# qPCR_pcb_breakout_ADG731BSUZ.net
KiCad netlist of a schematic drawn in EAGLE
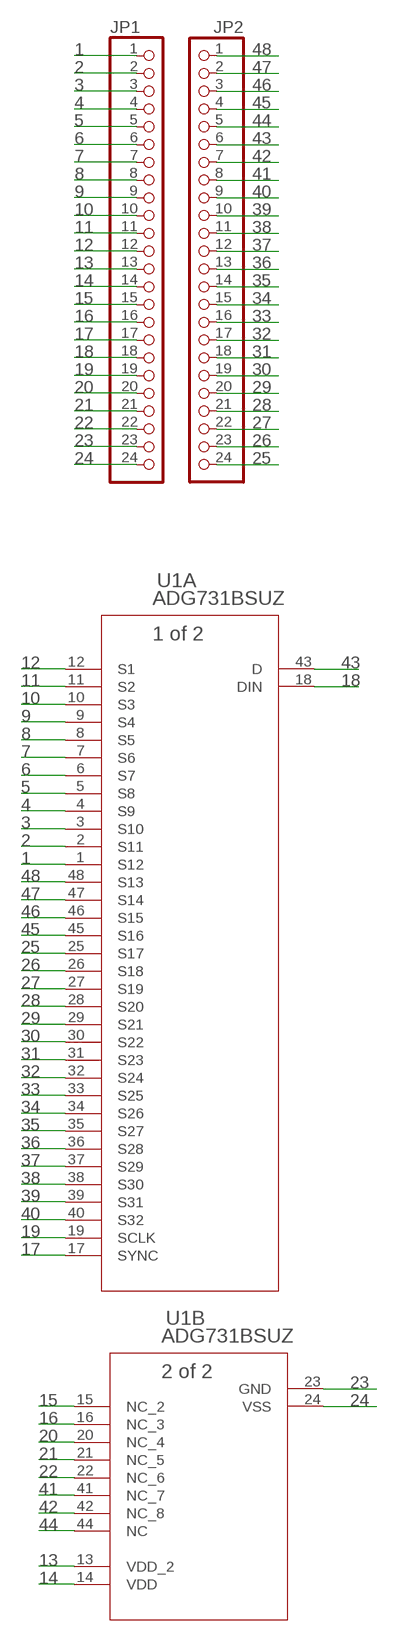
[diagram p0: schematic, sheet 1]

(export (version "E")
  (design (tool "Eeschema 10.0.6"))
  (components
    (comp (ref "JP1")
      (value "PINHD-1X24")
      (footprint "eagle-import:1X24")
      (libsource (lib "eagle-import") (part "PINHD-1X24"))
    )
    (comp (ref "JP2")
      (value "PINHD-1X24")
      (footprint "eagle-import:1X24")
      (libsource (lib "eagle-import") (part "PINHD-1X24"))
    )
    (comp (ref "U1")
      (value "ADG731BSUZ")
      (footprint "eagle-import:SU_48_ADI")
      (libsource (lib "eagle-import") (part "ADG731BSUZ"))
    )
  )
  (nets
    (net (code "1") (name "/1") (class "Default")
      (node (ref "JP1") (pin "1") (pinfunction "1_1") (pintype "passive"))
      (node (ref "U1") (pin "1") (pinfunction "S12_1") (pintype "passive"))
    )
    (net (code "2") (name "/2") (class "Default")
      (node (ref "JP1") (pin "2") (pinfunction "2_2") (pintype "passive"))
      (node (ref "U1") (pin "2") (pinfunction "S11_2") (pintype "passive"))
    )
    (net (code "3") (name "/3") (class "Default")
      (node (ref "JP1") (pin "3") (pinfunction "3_3") (pintype "passive"))
      (node (ref "U1") (pin "3") (pinfunction "S10_3") (pintype "passive"))
    )
    (net (code "4") (name "/4") (class "Default")
      (node (ref "JP1") (pin "4") (pinfunction "4_4") (pintype "passive"))
      (node (ref "U1") (pin "4") (pinfunction "S9_4") (pintype "passive"))
    )
    (net (code "5") (name "/5") (class "Default")
      (node (ref "JP1") (pin "5") (pinfunction "5_5") (pintype "passive"))
      (node (ref "U1") (pin "5") (pinfunction "S8_5") (pintype "passive"))
    )
    (net (code "6") (name "/6") (class "Default")
      (node (ref "JP1") (pin "6") (pinfunction "6_6") (pintype "passive"))
      (node (ref "U1") (pin "6") (pinfunction "S7_6") (pintype "passive"))
    )
    (net (code "7") (name "/7") (class "Default")
      (node (ref "JP1") (pin "7") (pinfunction "7_7") (pintype "passive"))
      (node (ref "U1") (pin "7") (pinfunction "S6_7") (pintype "passive"))
    )
    (net (code "8") (name "/8") (class "Default")
      (node (ref "JP1") (pin "8") (pinfunction "8_8") (pintype "passive"))
      (node (ref "U1") (pin "8") (pinfunction "S5_8") (pintype "passive"))
    )
    (net (code "9") (name "/9") (class "Default")
      (node (ref "JP1") (pin "9") (pinfunction "9_9") (pintype "passive"))
      (node (ref "U1") (pin "9") (pinfunction "S4_9") (pintype "passive"))
    )
    (net (code "10") (name "/10") (class "Default")
      (node (ref "JP1") (pin "10") (pinfunction "10_10") (pintype "passive"))
      (node (ref "U1") (pin "10") (pinfunction "S3_10") (pintype "passive"))
    )
    (net (code "11") (name "/11") (class "Default")
      (node (ref "JP1") (pin "11") (pinfunction "11_11") (pintype "passive"))
      (node (ref "U1") (pin "11") (pinfunction "S2_11") (pintype "passive"))
    )
    (net (code "12") (name "/12") (class "Default")
      (node (ref "JP1") (pin "12") (pinfunction "12_12") (pintype "passive"))
      (node (ref "U1") (pin "12") (pinfunction "S1_12") (pintype "passive"))
    )
    (net (code "13") (name "/13") (class "Default")
      (node (ref "JP1") (pin "13") (pinfunction "13_13") (pintype "passive"))
      (node (ref "U1") (pin "13") (pinfunction "VDD_2_13") (pintype "power_in"))
    )
    (net (code "14") (name "/14") (class "Default")
      (node (ref "JP1") (pin "14") (pinfunction "14_14") (pintype "passive"))
      (node (ref "U1") (pin "14") (pinfunction "VDD_14") (pintype "power_in"))
    )
    (net (code "15") (name "/15") (class "Default")
      (node (ref "JP1") (pin "15") (pinfunction "15_15") (pintype "passive"))
      (node (ref "U1") (pin "15") (pinfunction "NC_2_15") (pintype "passive"))
    )
    (net (code "16") (name "/16") (class "Default")
      (node (ref "JP1") (pin "16") (pinfunction "16_16") (pintype "passive"))
      (node (ref "U1") (pin "16") (pinfunction "NC_3_16") (pintype "passive"))
    )
    (net (code "17") (name "/17") (class "Default")
      (node (ref "JP1") (pin "17") (pinfunction "17_17") (pintype "passive"))
      (node (ref "U1") (pin "17") (pinfunction "SYNC_17") (pintype "passive"))
    )
    (net (code "18") (name "/18") (class "Default")
      (node (ref "JP1") (pin "18") (pinfunction "18_18") (pintype "passive"))
      (node (ref "U1") (pin "18") (pinfunction "DIN_18") (pintype "passive"))
    )
    (net (code "19") (name "/19") (class "Default")
      (node (ref "JP1") (pin "19") (pinfunction "19_19") (pintype "passive"))
      (node (ref "U1") (pin "19") (pinfunction "SCLK_19") (pintype "passive"))
    )
    (net (code "20") (name "/20") (class "Default")
      (node (ref "JP1") (pin "20") (pinfunction "20_20") (pintype "passive"))
      (node (ref "U1") (pin "20") (pinfunction "NC_4_20") (pintype "passive"))
    )
    (net (code "21") (name "/21") (class "Default")
      (node (ref "JP1") (pin "21") (pinfunction "21_21") (pintype "passive"))
      (node (ref "U1") (pin "21") (pinfunction "NC_5_21") (pintype "passive"))
    )
    (net (code "22") (name "/22") (class "Default")
      (node (ref "JP1") (pin "22") (pinfunction "22_22") (pintype "passive"))
      (node (ref "U1") (pin "22") (pinfunction "NC_6_22") (pintype "passive"))
    )
    (net (code "23") (name "/23") (class "Default")
      (node (ref "JP1") (pin "23") (pinfunction "23_23") (pintype "passive"))
      (node (ref "U1") (pin "23") (pinfunction "GND_23") (pintype "passive"))
    )
    (net (code "24") (name "/24") (class "Default")
      (node (ref "JP1") (pin "24") (pinfunction "24_24") (pintype "passive"))
      (node (ref "U1") (pin "24") (pinfunction "VSS_24") (pintype "power_in"))
    )
    (net (code "25") (name "/25") (class "Default")
      (node (ref "JP2") (pin "24") (pinfunction "24_24") (pintype "passive"))
      (node (ref "U1") (pin "25") (pinfunction "S17_25") (pintype "passive"))
    )
    (net (code "26") (name "/26") (class "Default")
      (node (ref "JP2") (pin "23") (pinfunction "23_23") (pintype "passive"))
      (node (ref "U1") (pin "26") (pinfunction "S18_26") (pintype "passive"))
    )
    (net (code "27") (name "/27") (class "Default")
      (node (ref "JP2") (pin "22") (pinfunction "22_22") (pintype "passive"))
      (node (ref "U1") (pin "27") (pinfunction "S19_27") (pintype "passive"))
    )
    (net (code "28") (name "/28") (class "Default")
      (node (ref "JP2") (pin "21") (pinfunction "21_21") (pintype "passive"))
      (node (ref "U1") (pin "28") (pinfunction "S20_28") (pintype "passive"))
    )
    (net (code "29") (name "/29") (class "Default")
      (node (ref "JP2") (pin "20") (pinfunction "20_20") (pintype "passive"))
      (node (ref "U1") (pin "29") (pinfunction "S21_29") (pintype "passive"))
    )
    (net (code "30") (name "/30") (class "Default")
      (node (ref "JP2") (pin "19") (pinfunction "19_19") (pintype "passive"))
      (node (ref "U1") (pin "30") (pinfunction "S22_30") (pintype "passive"))
    )
    (net (code "31") (name "/31") (class "Default")
      (node (ref "JP2") (pin "18") (pinfunction "18_18") (pintype "passive"))
      (node (ref "U1") (pin "31") (pinfunction "S23_31") (pintype "passive"))
    )
    (net (code "32") (name "/32") (class "Default")
      (node (ref "JP2") (pin "17") (pinfunction "17_17") (pintype "passive"))
      (node (ref "U1") (pin "32") (pinfunction "S24_32") (pintype "passive"))
    )
    (net (code "33") (name "/33") (class "Default")
      (node (ref "JP2") (pin "16") (pinfunction "16_16") (pintype "passive"))
      (node (ref "U1") (pin "33") (pinfunction "S25_33") (pintype "passive"))
    )
    (net (code "34") (name "/34") (class "Default")
      (node (ref "JP2") (pin "15") (pinfunction "15_15") (pintype "passive"))
      (node (ref "U1") (pin "34") (pinfunction "S26_34") (pintype "passive"))
    )
    (net (code "35") (name "/35") (class "Default")
      (node (ref "JP2") (pin "14") (pinfunction "14_14") (pintype "passive"))
      (node (ref "U1") (pin "35") (pinfunction "S27_35") (pintype "passive"))
    )
    (net (code "36") (name "/36") (class "Default")
      (node (ref "JP2") (pin "13") (pinfunction "13_13") (pintype "passive"))
      (node (ref "U1") (pin "36") (pinfunction "S28_36") (pintype "passive"))
    )
    (net (code "37") (name "/37") (class "Default")
      (node (ref "JP2") (pin "12") (pinfunction "12_12") (pintype "passive"))
      (node (ref "U1") (pin "37") (pinfunction "S29_37") (pintype "passive"))
    )
    (net (code "38") (name "/38") (class "Default")
      (node (ref "JP2") (pin "11") (pinfunction "11_11") (pintype "passive"))
      (node (ref "U1") (pin "38") (pinfunction "S30_38") (pintype "passive"))
    )
    (net (code "39") (name "/39") (class "Default")
      (node (ref "JP2") (pin "10") (pinfunction "10_10") (pintype "passive"))
      (node (ref "U1") (pin "39") (pinfunction "S31_39") (pintype "passive"))
    )
    (net (code "40") (name "/40") (class "Default")
      (node (ref "JP2") (pin "9") (pinfunction "9_9") (pintype "passive"))
      (node (ref "U1") (pin "40") (pinfunction "S32_40") (pintype "passive"))
    )
    (net (code "41") (name "/41") (class "Default")
      (node (ref "JP2") (pin "8") (pinfunction "8_8") (pintype "passive"))
      (node (ref "U1") (pin "41") (pinfunction "NC_7_41") (pintype "passive"))
    )
    (net (code "42") (name "/42") (class "Default")
      (node (ref "JP2") (pin "7") (pinfunction "7_7") (pintype "passive"))
      (node (ref "U1") (pin "42") (pinfunction "NC_8_42") (pintype "passive"))
    )
    (net (code "43") (name "/43") (class "Default")
      (node (ref "JP2") (pin "6") (pinfunction "6_6") (pintype "passive"))
      (node (ref "U1") (pin "43") (pinfunction "D_43") (pintype "passive"))
    )
    (net (code "44") (name "/44") (class "Default")
      (node (ref "JP2") (pin "5") (pinfunction "5_5") (pintype "passive"))
      (node (ref "U1") (pin "44") (pinfunction "NC_44") (pintype "passive"))
    )
    (net (code "45") (name "/45") (class "Default")
      (node (ref "JP2") (pin "4") (pinfunction "4_4") (pintype "passive"))
      (node (ref "U1") (pin "45") (pinfunction "S16_45") (pintype "passive"))
    )
    (net (code "46") (name "/46") (class "Default")
      (node (ref "JP2") (pin "3") (pinfunction "3_3") (pintype "passive"))
      (node (ref "U1") (pin "46") (pinfunction "S15_46") (pintype "passive"))
    )
    (net (code "47") (name "/47") (class "Default")
      (node (ref "JP2") (pin "2") (pinfunction "2_2") (pintype "passive"))
      (node (ref "U1") (pin "47") (pinfunction "S14_47") (pintype "passive"))
    )
    (net (code "48") (name "/48") (class "Default")
      (node (ref "JP2") (pin "1") (pinfunction "1_1") (pintype "passive"))
      (node (ref "U1") (pin "48") (pinfunction "S13_48") (pintype "passive"))
    )
  )
)
